# JacdacAccessSwitchInput_34.net
KiCad netlist of a schematic drawn in Altium Designer
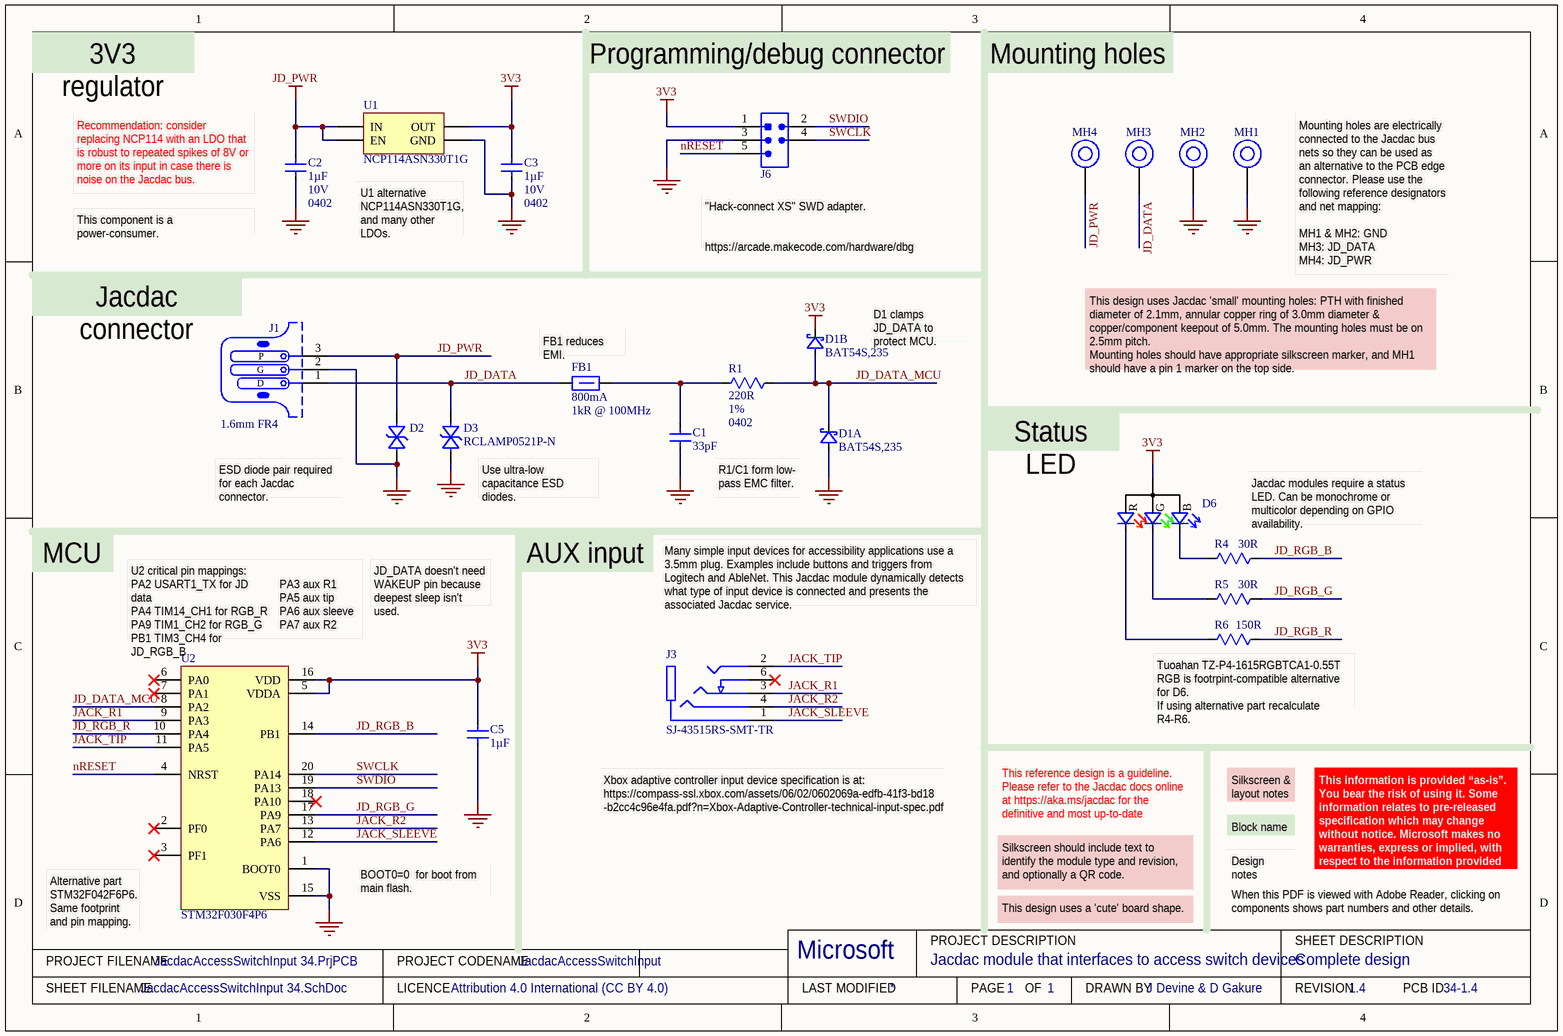
[diagram p0: JacdacAccessSwitchInput 34.SchDoc]

(export (version "E")
  (design (tool "Eeschema 10.0.6"))
  (components
    (comp (ref "C1")
      (value "CL05C330JB51PNC")
      (footprint "C0402_0.55MM - without outline")
      (description "CAP CER 33PF 50V NP0 0402")
      (fields
        (field (name "MANUFACTURER") "Samsung")
        (field (name "TOLERANCE") "5%")
        (field (name "CAPACITANCE") "33pF")
        (field (name "CHECKED") "?")
        (field (name "CREATED") "DG")
      )
      (libsource (lib "Samsung") (part "CL05C330JB51PNC"))
    )
    (comp (ref "C2")
      (value "CL05A105KP5NNNC")
      (footprint "C0402_0.55MM - without outline")
      (description "CAP CER 1UF 10V X5R 0402")
      (fields
        (field (name "MANUFACTURER") "Samsung")
        (field (name "TOLERANCE") "10%")
        (field (name "CAPACITANCE") "1µF")
        (field (name "VOLTAGE RATING") "10V")
        (field (name "CASE CODE (IMPERIAL)") "0402")
        (field (name "CREATED") "DG")
        (field (name "CHECKED") "?")
      )
      (libsource (lib "Samsung") (part "CL05A105KP5NNNC"))
    )
    (comp (ref "C3")
      (value "CL05A105KP5NNNC")
      (footprint "C0402_0.55MM - without outline")
      (description "CAP CER 1UF 10V X5R 0402")
      (fields
        (field (name "MANUFACTURER") "Samsung")
        (field (name "TOLERANCE") "10%")
        (field (name "CAPACITANCE") "1µF")
        (field (name "VOLTAGE RATING") "10V")
        (field (name "CASE CODE (IMPERIAL)") "0402")
        (field (name "CREATED") "DG")
        (field (name "CHECKED") "?")
      )
      (libsource (lib "Samsung") (part "CL05A105KP5NNNC"))
    )
    (comp (ref "C5")
      (value "CL05A105KP5NNNC")
      (footprint "C0402_0.55MM - without outline")
      (description "CAP CER 1UF 10V X5R 0402")
      (fields
        (field (name "MANUFACTURER") "Samsung")
        (field (name "TOLERANCE") "10%")
        (field (name "CAPACITANCE") "1µF")
        (field (name "CREATED") "DG")
        (field (name "CHECKED") "?")
      )
      (libsource (lib "Samsung") (part "CL05A105KP5NNNC"))
    )
    (comp (ref "D1")
      (value "BAT54S")
      (footprint "NXP-BAT54S-TO-236AB - without outline")
      (description "DIODE ARRAY SCHOTTKY 30V SOT23")
      (fields (field (name "MANUFACTURER") "Nexperia") (field (name "MANUFACTURER PART NUMBER") "BAT54S,235"))
      (libsource (lib "NXP") (part "BAT54S"))
    )
    (comp (ref "D2")
      (value "RCLAMP0521P-N")
      (footprint "TVS 0402 - L")
      (description "Bidirectional 5V (Max) 6V 16V 3.5A (8/20us) 0402 TVS RoHS")
      (fields
        (field (name "MANUFACTURER") "Born Semiconductor")
        (field (name "CREATED BY") "D Gakure")
        (field (name "CHECKED BY") "?")
      )
      (libsource (lib "BornSemiconductor") (part "RCLAMP0521P-N"))
    )
    (comp (ref "D3")
      (value "RCLAMP0521P-N")
      (footprint "TVS 0402 - L")
      (description "Bidirectional 5V (Max) 6V 16V 3.5A (8/20us) 0402 TVS RoHS")
      (fields
        (field (name "MANUFACTURER") "Born Semiconductor")
        (field (name "MANUFACTURER PART NUMBER") "RCLAMP0521P-N")
        (field (name "CREATED BY") "D Gakure")
        (field (name "CHECKED BY") "?")
      )
      (libsource (lib "BornSemiconductor") (part "RCLAMP0521P-N"))
    )
    (comp (ref "D6")
      (value "HSMF-C114")
      (footprint "HSMF-C114")
      (fields
        (field (name "MANUFACTURER") "Broadcom Avago")
        (field (name "CREATED BY") "D. Gakure")
        (field (name "CHECKED BY") "?")
      )
      (libsource (lib "BroadcomLimited") (part "HSMF-C114"))
    )
    (comp (ref "FB1")
      (value "TDK MPZ1608S102ATA00")
      (footprint "TDK MPZ1608 0.8mm - without outline")
      (description "0603 1k@100MHz 0.8A chip")
      (fields
        (field (name "TOLERANCE") "25%")
        (field (name "MANUFACTURER") "TDK")
        (field (name "CURRENT RATING") "800mA")
        (field (name "IMPEDANCE") "1kR @ 100MHz")
      )
      (libsource (lib "TDK") (part "TDK MPZ1608S102ATA00"))
    )
    (comp (ref "J1")
      (value "3 pin JACDAC edge connector")
      (footprint "JACDAC_EDGE_CONNECTOR_NO_TRACES")
      (description "3 pin Jacdac edge connector 1.27mm pitch")
      (fields
        (field (name "MANUFACTURER PART NUMBER") "JACDAC_EDGE_CONNECTOR")
        (field (name "PCB TYPE") "1.6mm FR4")
        (field (name "CHECKED BY") "?")
        (field (name "CREATED BY") "D. Gakure")
      )
      (libsource (lib "generic-con") (part "Jacdac edge connector"))
    )
    (comp (ref "J3")
      (value "SJ2-43515RS-SMT")
      (footprint "SJ-43515RS-SMT-TR")
      (description "4-way 3.5mm jack socket SMD R/A TRRS")
      (fields
        (field (name "MANUFACTURER") "CUI")
        (field (name "MANUFACTURER PART NUMBER") "SJ-43515RS-SMT-TR")
      )
      (libsource (lib "CUI") (part "SJ2-43515RS-SMT"))
    )
    (comp (ref "J6")
      (value "Hack Connect Mini 1.27 mm pitch 2-row")
      (footprint "HACK_CONNECT_MINI_5_X_1_27")
      (libsource (lib "generic-con") (part "HACK_CONNECT_MINI"))
    )
    (comp (ref "MH1")
      (value "MH_5.0MMK_3.0MMC_2.1MMD_PTH")
      (footprint "MH_5.0MMK_3.0MMC_2.1MMD_PTH:MH_5.0MMK_3.0MMC_2.1MMD_PTH")
      (description "Mounting Hole 5.0mm keepout, 3.0mm annualar ring and 2.1mm Drill PTH")
      (libsource (lib "generic") (part "MH_5.0MMK_3.0MMC_2.1MMD_PTH"))
    )
    (comp (ref "MH2")
      (value "MH_5.0MMK_3.0MMC_2.1MMD_PTH")
      (footprint "MH_5.0MMK_3.0MMC_2.1MMD_PTH:MH_5.0MMK_3.0MMC_2.1MMD_PTH")
      (description "Mounting Hole 5.0mm keepout, 3.0mm annualar ring and 2.1mm Drill PTH")
      (libsource (lib "generic") (part "MH_5.0MMK_3.0MMC_2.1MMD_PTH"))
    )
    (comp (ref "MH3")
      (value "MH_5.0MMK_3.0MMC_2.1MMD_PTH")
      (footprint "MH_5.0MMK_3.0MMC_2.1MMD_PTH:MH_5.0MMK_3.0MMC_2.1MMD_PTH")
      (description "Mounting Hole 5.0mm keepout, 3.0mm annualar ring and 2.1mm Drill PTH")
      (libsource (lib "generic") (part "MH_5.0MMK_3.0MMC_2.1MMD_PTH"))
    )
    (comp (ref "MH4")
      (value "MH_5.0MMK_3.0MMC_2.1MMD_PTH")
      (footprint "MH_5.0MMK_3.0MMC_2.1MMD_PTH:MH_5.0MMK_3.0MMC_2.1MMD_PTH")
      (description "Mounting Hole 5.0mm keepout, 3.0mm annualar ring and 2.1mm Drill PTH")
      (libsource (lib "generic") (part "MH_5.0MMK_3.0MMC_2.1MMD_PTH"))
    )
    (comp (ref "R1")
      (value "0402WGF2200TCE")
      (footprint "UNIROYAL-0402:R0402 - Without outline")
      (description "RES SMD 220 OHM 1% 1/16W 0402")
      (fields
        (field (name "MANUFACTURER") "Uniroyal Elec")
        (field (name "RESISTANCE") "220R")
        (field (name "TOLERANCE") "1%")
        (field (name "CASE CODE (IMPERIAL)") "0402")
      )
      (libsource (lib "UniroyalElec") (part "0402WGF2200TCE"))
    )
    (comp (ref "R4")
      (value "0402WGF300JTCE")
      (footprint "UNIROYAL-0402:R0402 - Without outline")
      (description "RES SMD 30 OHM 1% 1/16W 0402")
      (fields
        (field (name "MANUFACTURER") "Uniroyal Elec")
        (field (name "RESISTANCE") "30R")
        (field (name "TOLERANCE") "1%")
      )
      (libsource (lib "UniroyalElec") (part "0402WGF300JTCE"))
    )
    (comp (ref "R5")
      (value "0402WGF300JTCE")
      (footprint "UNIROYAL-0402:R0402 - Without outline")
      (description "RES SMD 30 OHM 1% 1/16W 0402")
      (fields
        (field (name "MANUFACTURER") "Uniroyal Elec")
        (field (name "RESISTANCE") "30R")
        (field (name "TOLERANCE") "1%")
      )
      (libsource (lib "UniroyalElec") (part "0402WGF300JTCE"))
    )
    (comp (ref "R6")
      (value "0402WGF1500TCE")
      (footprint "UNIROYAL-0402:R0402 - Without outline")
      (description "RES SMD 150 OHM 1% 1/16W 0402")
      (fields
        (field (name "MANUFACTURER") "Uniroyal Elec")
        (field (name "RESISTANCE") "150R")
        (field (name "TOLERANCE") "1%")
      )
      (libsource (lib "UniroyalElec") (part "0402WGF1500TCE"))
    )
    (comp (ref "U1")
      (value "LDO 3.3V/300 mA")
      (footprint "ON_SEMI-SOT23-5 - without outline")
      (fields
        (field (name "MANUFACTURER") "ON Semiconductor")
        (field (name "MANUFACTURER PART NUMBER") "NCP114ASN330T1G")
        (field (name "CREATED") "DG")
        (field (name "CHECKED") "?")
      )
      (libsource (lib "OnSemiconductor") (part "NCP114ASN330T1G"))
    )
    (comp (ref "U2")
      (value "STM32F030F4P6")
      (footprint "20-TSSOP")
      (fields
        (field (name "MANUFACTURER") "STMicroelectronics")
        (field (name "MANUFACTURER PART NUMBER") "STM32F030F4P6")
        (field (name "CREATED") "DG")
        (field (name "CHECKED") "?")
      )
      (libsource (lib "ST") (part "ST STM32F030F4P6"))
    )
  )
  (nets
    (net (code "1") (name "/JACK_R1") (class "Default")
      (node (ref "J3") (pin "3") (pinfunction "3_3") (pintype "passive"))
      (node (ref "U2") (pin "9") (pinfunction "PA3_9") (pintype "passive"))
    )
    (net (code "2") (name "/JACK_R2") (class "Default")
      (node (ref "J3") (pin "4") (pinfunction "4_4") (pintype "passive"))
      (node (ref "U2") (pin "13") (pinfunction "PA7_13") (pintype "passive"))
    )
    (net (code "3") (name "/JACK_SLEEVE") (class "Default")
      (node (ref "J3") (pin "1") (pinfunction "1_1") (pintype "passive"))
      (node (ref "U2") (pin "12") (pinfunction "PA6_12") (pintype "passive"))
    )
    (net (code "4") (name "/JACK_TIP") (class "Default")
      (node (ref "J3") (pin "2") (pinfunction "2_2") (pintype "passive"))
      (node (ref "U2") (pin "11") (pinfunction "PA5_11") (pintype "passive"))
    )
    (net (code "5") (name "/JD_DATA") (class "Default")
      (node (ref "D3") (pin "1") (pinfunction "K_1") (pintype "passive"))
      (node (ref "FB1") (pin "1") (pinfunction "1_1") (pintype "passive"))
      (node (ref "J1") (pin "1") (pinfunction "D_1") (pintype "passive"))
      (node (ref "MH3") (pin "1") (pinfunction "1_1") (pintype "passive"))
    )
    (net (code "6") (name "/JD_DATA_MCU") (class "Default")
      (node (ref "D1") (pin "3") (pinfunction "K_3") (pintype "passive"))
      (node (ref "R1") (pin "1") (pinfunction "1_1") (pintype "passive"))
      (node (ref "U2") (pin "8") (pinfunction "PA2_8") (pintype "passive"))
    )
    (net (code "7") (name "/JD_RGB_B") (class "Default")
      (node (ref "R4") (pin "2") (pinfunction "2_2") (pintype "passive"))
      (node (ref "U2") (pin "14") (pinfunction "PB1_14") (pintype "passive"))
    )
    (net (code "8") (name "/JD_RGB_G") (class "Default")
      (node (ref "R5") (pin "2") (pinfunction "2_2") (pintype "passive"))
      (node (ref "U2") (pin "17") (pinfunction "PA9_17") (pintype "passive"))
    )
    (net (code "9") (name "/JD_RGB_R") (class "Default")
      (node (ref "R6") (pin "2") (pinfunction "2_2") (pintype "passive"))
      (node (ref "U2") (pin "10") (pinfunction "PA4_10") (pintype "passive"))
    )
    (net (code "10") (name "/SWCLK") (class "Default")
      (node (ref "J6") (pin "4") (pinfunction "SWCLK_4") (pintype "passive"))
      (node (ref "U2") (pin "20") (pinfunction "PA14_20") (pintype "passive"))
    )
    (net (code "11") (name "/SWDIO") (class "Default")
      (node (ref "J6") (pin "2") (pinfunction "SWDIO_2") (pintype "passive"))
      (node (ref "U2") (pin "19") (pinfunction "PA13_19") (pintype "passive"))
    )
    (net (code "12") (name "/nRESET") (class "Default")
      (node (ref "J6") (pin "5") (pinfunction "RESET_5") (pintype "passive"))
      (node (ref "U2") (pin "4") (pinfunction "NRST_4") (pintype "passive"))
    )
    (net (code "13") (name "3V3") (class "Default")
      (node (ref "C3") (pin "2") (pinfunction "2_2") (pintype "passive"))
      (node (ref "C5") (pin "2") (pinfunction "2_2") (pintype "passive"))
      (node (ref "D1") (pin "2") (pinfunction "K_2") (pintype "passive"))
      (node (ref "D6") (pin "1") (pinfunction "A_1") (pintype "passive"))
      (node (ref "J6") (pin "1") (pinfunction "VCC_1") (pintype "passive"))
      (node (ref "U1") (pin "5") (pinfunction "OUT_5") (pintype "passive"))
      (node (ref "U2") (pin "16") (pinfunction "VDD_16") (pintype "power_in"))
      (node (ref "U2") (pin "5") (pinfunction "VDDA_5") (pintype "power_in"))
    )
    (net (code "14") (name "GND") (class "Default")
      (node (ref "C1") (pin "1") (pinfunction "1_1") (pintype "passive"))
      (node (ref "C2") (pin "1") (pinfunction "1_1") (pintype "passive"))
      (node (ref "C3") (pin "1") (pinfunction "1_1") (pintype "passive"))
      (node (ref "C5") (pin "1") (pinfunction "1_1") (pintype "passive"))
      (node (ref "D1") (pin "1") (pinfunction "A_1") (pintype "passive"))
      (node (ref "D2") (pin "2") (pinfunction "A_2") (pintype "passive"))
      (node (ref "D3") (pin "2") (pinfunction "A_2") (pintype "passive"))
      (node (ref "J1") (pin "2") (pinfunction "G_2") (pintype "passive"))
      (node (ref "J6") (pin "3") (pinfunction "GND_3") (pintype "passive"))
      (node (ref "MH1") (pin "1") (pinfunction "1_1") (pintype "passive"))
      (node (ref "MH2") (pin "1") (pinfunction "1_1") (pintype "passive"))
      (node (ref "U1") (pin "2") (pinfunction "GND_2") (pintype "passive"))
      (node (ref "U2") (pin "1") (pinfunction "BOOT0_1") (pintype "passive"))
      (node (ref "U2") (pin "15") (pinfunction "VSS_15") (pintype "power_in"))
    )
    (net (code "15") (name "JD_PWR") (class "Default")
      (node (ref "C2") (pin "2") (pinfunction "2_2") (pintype "passive"))
      (node (ref "D2") (pin "1") (pinfunction "K_1") (pintype "passive"))
      (node (ref "J1") (pin "3") (pinfunction "P_3") (pintype "passive"))
      (node (ref "MH4") (pin "1") (pinfunction "1_1") (pintype "passive"))
      (node (ref "U1") (pin "1") (pinfunction "IN_1") (pintype "passive"))
      (node (ref "U1") (pin "3") (pinfunction "EN_3") (pintype "passive"))
    )
    (net (code "16") (name "Net-(C1-Pad2)") (class "Default")
      (node (ref "C1") (pin "2") (pinfunction "2_2") (pintype "passive"))
      (node (ref "FB1") (pin "2") (pinfunction "2_2") (pintype "passive"))
      (node (ref "R1") (pin "2") (pinfunction "2_2") (pintype "passive"))
    )
    (net (code "17") (name "Net-(D6-B)") (class "Default")
      (node (ref "D6") (pin "4") (pinfunction "B_4") (pintype "passive"))
      (node (ref "R4") (pin "1") (pinfunction "1_1") (pintype "passive"))
    )
    (net (code "18") (name "Net-(D6-G)") (class "Default")
      (node (ref "D6") (pin "3") (pinfunction "G_3") (pintype "passive"))
      (node (ref "R5") (pin "1") (pinfunction "1_1") (pintype "passive"))
    )
    (net (code "19") (name "Net-(D6-R)") (class "Default")
      (node (ref "D6") (pin "2") (pinfunction "R_2") (pintype "passive"))
      (node (ref "R6") (pin "1") (pinfunction "1_1") (pintype "passive"))
    )
    (net (code "20") (name "unconnected-(J3-Pad6)") (class "Default")
      (node (ref "J3") (pin "6") (pinfunction "6_6") (pintype "passive+no_connect"))
    )
    (net (code "21") (name "unconnected-(U2-PA0-Pad6)") (class "Default")
      (node (ref "U2") (pin "6") (pinfunction "PA0_6") (pintype "passive+no_connect"))
    )
    (net (code "22") (name "unconnected-(U2-PA1-Pad7)") (class "Default")
      (node (ref "U2") (pin "7") (pinfunction "PA1_7") (pintype "passive+no_connect"))
    )
    (net (code "23") (name "unconnected-(U2-PA10-Pad18)") (class "Default")
      (node (ref "U2") (pin "18") (pinfunction "PA10_18") (pintype "passive+no_connect"))
    )
    (net (code "24") (name "unconnected-(U2-PF0-Pad2)") (class "Default")
      (node (ref "U2") (pin "2") (pinfunction "PF0_2") (pintype "passive+no_connect"))
    )
    (net (code "25") (name "unconnected-(U2-PF1-Pad3)") (class "Default")
      (node (ref "U2") (pin "3") (pinfunction "PF1_3") (pintype "passive+no_connect"))
    )
  )
)
